# design.net
KiCad netlist of a schematic drawn in Altium Designer
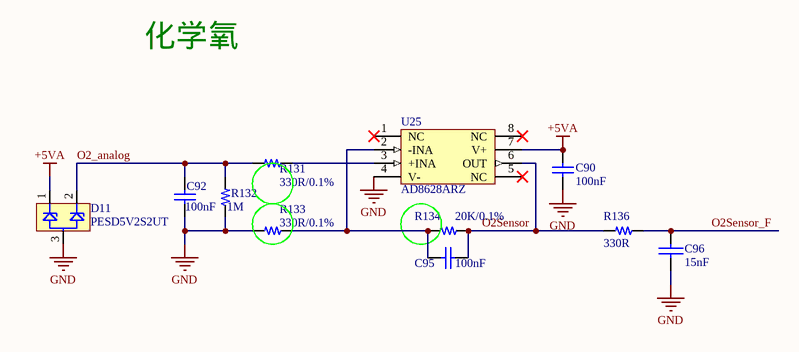
[diagram p0: 氧传感器.SchDoc]

(export (version "E")
  (design (tool "Eeschema 10.0.6"))
  (components
    (comp (ref "C90")
      (value "100nF")
      (footprint "C-0603")
      (description "贴片瓷介电容100nF±5%,0805")
      (libsource (lib "电容") (part "100nF_1"))
    )
    (comp (ref "C92")
      (value "100nF")
      (footprint "C-0603")
      (description "贴片瓷介电容100nF±5%,0805")
      (libsource (lib "电容") (part "100nF_1"))
    )
    (comp (ref "C95")
      (value "100nF")
      (footprint "C-0603")
      (description "贴片瓷介电容100nF±5%,0805")
      (libsource (lib "电容") (part "100nF_1"))
    )
    (comp (ref "C96")
      (value "15nF")
      (footprint "C-0603")
      (description "Capacitor")
      (libsource (lib "*") (part "CAP"))
    )
    (comp (ref "D11") (value "PESD5V2S2UT") (footprint "sot23-3") (libsource (lib "IC") (part "PESDxS2UT")))
    (comp (ref "R131")
      (value "330R/0.1%")
      (footprint "R-0603")
      (description "国巨RC0805FR-07330R")
      (libsource (lib "电阻") (part "330Ω_1"))
    )
    (comp (ref "R132")
      (value "1M")
      (footprint "R-0603")
      (description "国巨RC0805FR-071M")
      (libsource (lib "电阻") (part "1M_1"))
    )
    (comp (ref "R133")
      (value "330R/0.1%")
      (footprint "R-0603")
      (description "国巨RC0805FR-07330R")
      (libsource (lib "电阻") (part "330Ω_1"))
    )
    (comp (ref "R134")
      (value "20K/0.1%")
      (footprint "R-0603")
      (description "国巨RC0805FR-0712K")
      (libsource (lib "电阻") (part "12K_1"))
    )
    (comp (ref "R136") (value "330R") (footprint "R-0603") (libsource (lib "Device") (part "R-0603")))
    (comp (ref "U25") (value "AD8628ARZ") (footprint "SOIC8") (libsource (lib "IC") (part "AD8628ARZ")))
  )
  (nets
    (net (code "1") (name "+5VA") (class "Default")
      (node (ref "C90") (pin "1") (pinfunction "1_1") (pintype "passive"))
      (node (ref "D11") (pin "1") (pinfunction "1_1") (pintype "passive"))
      (node (ref "U25") (pin "7") (pinfunction "V+_7") (pintype "power_in"))
    )
    (net (code "2") (name "/O2Sensor") (class "Default")
      (node (ref "C95") (pin "2") (pinfunction "2_2") (pintype "passive"))
      (node (ref "R134") (pin "2") (pinfunction "BOT_2") (pintype "passive"))
      (node (ref "R136") (pin "2") (pinfunction "2_2") (pintype "passive"))
      (node (ref "U25") (pin "6") (pinfunction "OUT_6") (pintype "output"))
    )
    (net (code "3") (name "/O2Sensor_F") (class "Default")
      (node (ref "C96") (pin "2") (pinfunction "2_2") (pintype "passive"))
      (node (ref "R136") (pin "1") (pinfunction "1_1") (pintype "passive"))
    )
    (net (code "4") (name "/O2_analog") (class "Default")
      (node (ref "C92") (pin "2") (pinfunction "2_2") (pintype "passive"))
      (node (ref "D11") (pin "2") (pinfunction "2_2") (pintype "passive"))
      (node (ref "R131") (pin "1") (pinfunction "TOP_1") (pintype "passive"))
      (node (ref "R132") (pin "2") (pinfunction "BOT_2") (pintype "passive"))
    )
    (net (code "5") (name "GND") (class "Default")
      (node (ref "C90") (pin "2") (pinfunction "2_2") (pintype "passive"))
      (node (ref "C92") (pin "1") (pinfunction "1_1") (pintype "passive"))
      (node (ref "C96") (pin "1") (pinfunction "1_1") (pintype "passive"))
      (node (ref "D11") (pin "3") (pinfunction "3_3") (pintype "passive"))
      (node (ref "R132") (pin "1") (pinfunction "TOP_1") (pintype "passive"))
      (node (ref "R133") (pin "1") (pinfunction "TOP_1") (pintype "passive"))
      (node (ref "U25") (pin "4") (pinfunction "V-_4") (pintype "passive"))
    )
    (net (code "6") (name "Net-(R131-BOT)") (class "Default")
      (node (ref "R131") (pin "2") (pinfunction "BOT_2") (pintype "passive"))
      (node (ref "U25") (pin "3") (pinfunction "+INA_3") (pintype "input"))
    )
    (net (code "7") (name "Net-(R133-BOT)") (class "Default")
      (node (ref "C95") (pin "1") (pinfunction "1_1") (pintype "passive"))
      (node (ref "R133") (pin "2") (pinfunction "BOT_2") (pintype "passive"))
      (node (ref "R134") (pin "1") (pinfunction "TOP_1") (pintype "passive"))
      (node (ref "U25") (pin "2") (pinfunction "-INA_2") (pintype "input"))
    )
    (net (code "8") (name "unconnected-(U25-NC-Pad1)") (class "Default")
      (node (ref "U25") (pin "1") (pinfunction "NC_1") (pintype "tri_state+no_connect"))
    )
    (net (code "9") (name "unconnected-(U25-NC-Pad5)") (class "Default")
      (node (ref "U25") (pin "5") (pinfunction "NC_5") (pintype "tri_state+no_connect"))
    )
    (net (code "10") (name "unconnected-(U25-NC-Pad8)") (class "Default")
      (node (ref "U25") (pin "8") (pinfunction "NC_8") (pintype "tri_state+no_connect"))
    )
  )
)
